# BAT.net
KiCad netlist of a schematic drawn in Altium Designer
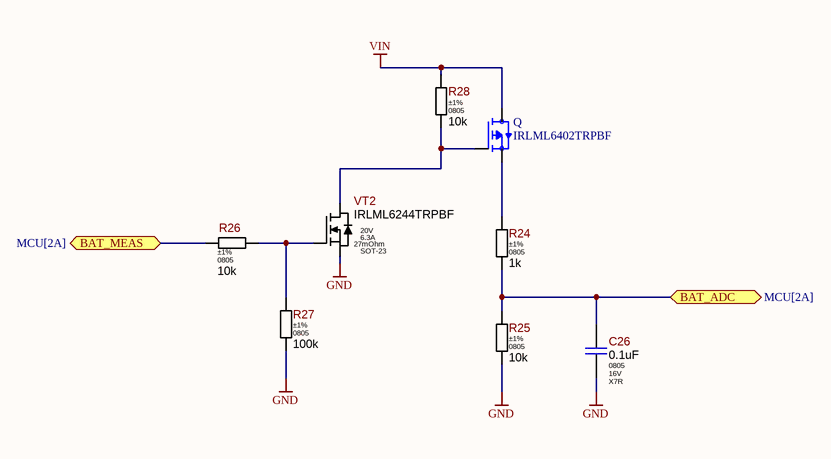
[diagram p0: BAT.SchDoc]

(export (version "E")
  (design (tool "Eeschema 10.0.6"))
  (components
    (comp (ref "C26")
      (value "0.1uF")
      (footprint "ALL:C0805")
      (fields
        (field (name "PACKAGE") "0805")
        (field (name "VOLTAGE") "16V")
        (field (name "DIELECTRIC TYPE") "X7R")
        (field (name "PART NUMBER") "GRM155R71C104JA88J")
        (field (name "MANUFACTURER") "Murata Electronics")
        (field (name "TOLERANCE") "±5%")
      )
      (libsource (lib "Miscellaneous Devices") (part "Capacitor-NonPolar"))
    )
    (comp (ref "Q")
      (value "IRLML6402TRPBF")
      (footprint "SOT95P237X112-3N")
      (fields (field (name "MF") "Infineon"))
      (libsource (lib "IRLML6402TRPBF") (part "IRLML6402TRPBF"))
    )
    (comp (ref "R24")
      (value "1k")
      (footprint "ALL:R0805")
      (description "10 kOhms ±1% 1/16W 0402 Thick Film Resistor")
      (fields
        (field (name "TOLERANCE") "±1%")
        (field (name "PACKAGE") "0805")
        (field (name "PART NUMBER") "RC0402FR-0710KL")
        (field (name "MANUFACTURER") "Yageo")
      )
      (libsource (lib "Miscellaneous Devices") (part "Resistor"))
    )
    (comp (ref "R25")
      (value "10k")
      (footprint "ALL:R0805")
      (description "10 kOhms ±1% 1/16W 0402 Thick Film Resistor")
      (fields
        (field (name "TOLERANCE") "±1%")
        (field (name "PACKAGE") "0805")
        (field (name "PART NUMBER") "RC0402FR-0710KL")
        (field (name "MANUFACTURER") "Yageo")
      )
      (libsource (lib "Miscellaneous Devices") (part "Resistor"))
    )
    (comp (ref "R26")
      (value "10k")
      (footprint "R0805")
      (description "10 kOhms ±1% 1/16W 0402 Thick Film Resistor")
      (fields
        (field (name "TOLERANCE") "±1%")
        (field (name "PACKAGE") "0805")
        (field (name "PART NUMBER") "RC0402FR-0710KL")
        (field (name "MANUFACTURER") "Yageo")
      )
      (libsource (lib "Miscellaneous Devices") (part "Resistor"))
    )
    (comp (ref "R27")
      (value "100k")
      (footprint "R0805")
      (description "10 kOhms ±1% 1/16W 0402 Thick Film Resistor")
      (fields
        (field (name "TOLERANCE") "±1%")
        (field (name "PACKAGE") "0805")
        (field (name "PART NUMBER") "RC0402FR-0710KL")
        (field (name "MANUFACTURER") "Yageo")
      )
      (libsource (lib "Miscellaneous Devices") (part "Resistor"))
    )
    (comp (ref "R28")
      (value "10k")
      (footprint "R0805")
      (description "10 kOhms ±1% 1/16W 0402 Thick Film Resistor")
      (fields
        (field (name "TOLERANCE") "±1%")
        (field (name "PACKAGE") "0805")
        (field (name "PART NUMBER") "RC0402FR-0710KL")
        (field (name "MANUFACTURER") "Yageo")
      )
      (libsource (lib "Miscellaneous Devices") (part "Resistor"))
    )
    (comp (ref "VT2")
      (value "IRLML6244")
      (footprint "IRLMT")
      (description "20V, 6.3A max N-Channel HEXFET MOSFET, 21mOhm @ Vgs = 4.5V")
      (fields
        (field (name "PART NUMBER") "IRLML6244TRPBF")
        (field (name "VDS") "20V")
        (field (name "ID") "6.3A")
        (field (name "RDS") "27mOhm")
        (field (name "PACKAGE") "SOT-23")
        (field (name "MANUFACTURER") "Infineon Technologies")
      )
      (libsource (lib "Miscellaneous Devices") (part "MOSFET-N-Channel"))
    )
  )
  (nets
    (net (code "1") (name "/BAT_ADC") (class "Default")
      (node (ref "C26") (pin "1") (pinfunction "1_1") (pintype "passive"))
      (node (ref "R24") (pin "2") (pintype "passive"))
      (node (ref "R25") (pin "1") (pintype "passive"))
    )
    (net (code "2") (name "/BAT_MEAS") (class "Default") (node (ref "R26") (pin "1") (pintype "passive")))
    (net (code "3") (name "GND") (class "Default")
      (node (ref "C26") (pin "2") (pinfunction "2_2") (pintype "passive"))
      (node (ref "R25") (pin "2") (pintype "passive"))
      (node (ref "R27") (pin "2") (pintype "passive"))
      (node (ref "VT2") (pin "2") (pinfunction "S_2") (pintype "passive"))
    )
    (net (code "4") (name "Net-(Q-G)") (class "Default")
      (node (ref "Q") (pin "1") (pinfunction "G_1") (pintype "passive"))
      (node (ref "R28") (pin "2") (pintype "passive"))
      (node (ref "VT2") (pin "3") (pinfunction "D_3") (pintype "passive"))
    )
    (net (code "5") (name "Net-(Q-S)") (class "Default")
      (node (ref "Q") (pin "2") (pinfunction "S_2") (pintype "passive"))
      (node (ref "R24") (pin "1") (pintype "passive"))
    )
    (net (code "6") (name "Net-(VT2-G)") (class "Default")
      (node (ref "R26") (pin "2") (pintype "passive"))
      (node (ref "R27") (pin "1") (pintype "passive"))
      (node (ref "VT2") (pin "1") (pinfunction "G_1") (pintype "passive"))
    )
    (net (code "7") (name "VIN") (class "Default")
      (node (ref "Q") (pin "3") (pinfunction "D_3") (pintype "passive"))
      (node (ref "R28") (pin "1") (pintype "passive"))
    )
  )
)
